# Arduino_Programmer.net
KiCad netlist of a schematic drawn in EAGLE
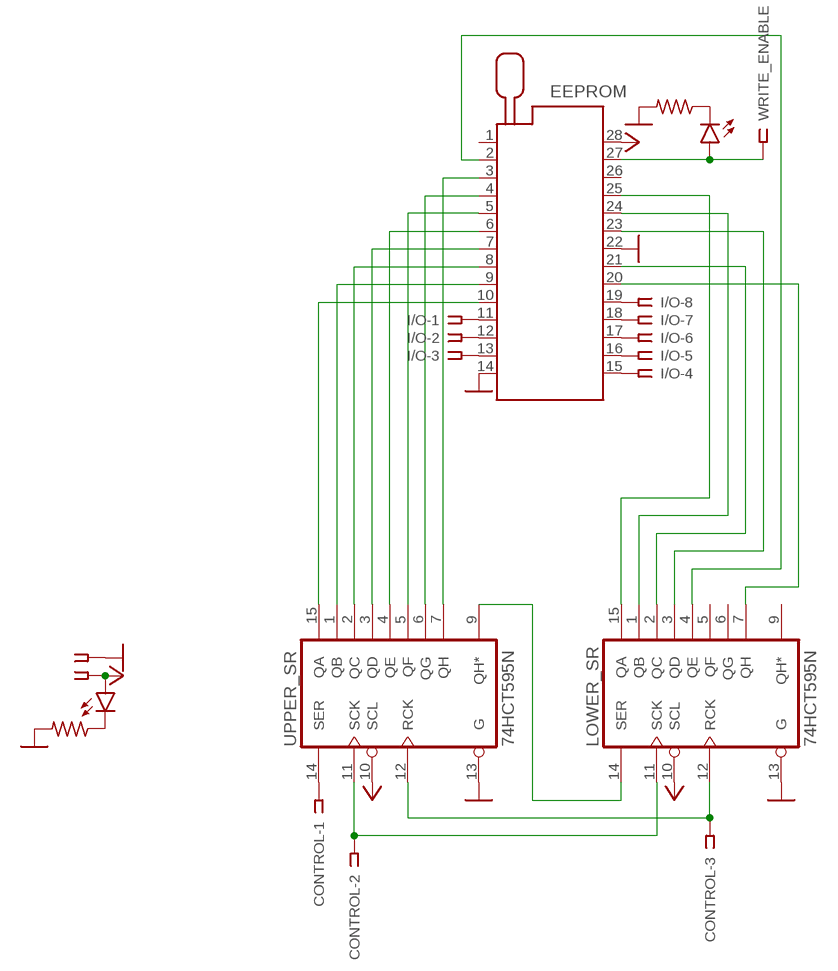
[diagram p0: schematic, sheet 1]

(export (version "E")
  (design (tool "Eeschema 10.0.6"))
  (components
    (comp (ref "CLK")
      (value "LED5MM")
      (footprint "eagle-import:LED5MM")
      (libsource (lib "eagle-import") (part "LED5MM"))
    )
    (comp (ref "CONTROL")
      (value "SSW-101-02-G-T")
      (footprint "eagle-import:SSW-101-02-G-T")
      (fields (field (name "MF") "Samtec Inc."))
      (libsource (lib "eagle-import") (part "SSW-101-02-G-T"))
    )
    (comp (ref "EEPROM")
      (value "228-1277-00-0602J")
      (footprint "eagle-import:228-1277-00-0602J")
      (fields (field (name "MF") "3M"))
      (libsource (lib "eagle-import") (part "228-?00-0602J1277-"))
    )
    (comp (ref "I/O")
      (value "SSW-108-02-G-S")
      (footprint "eagle-import:SSW-108-02-G-S")
      (fields (field (name "MF") "Samtec Inc."))
      (libsource (lib "eagle-import") (part "SSW-108-02-G-S"))
    )
    (comp (ref "LOWER_SR")
      (value "74HCT595N")
      (footprint "eagle-import:DIL16")
      (libsource (lib "eagle-import") (part "74595NHCT"))
    )
    (comp (ref "POWER")
      (value "LED5MM")
      (footprint "eagle-import:LED5MM")
      (libsource (lib "eagle-import") (part "LED5MM"))
    )
    (comp (ref "R1")
      (value "R-US_0204/7")
      (footprint "eagle-import:0204_7")
      (libsource (lib "eagle-import") (part "R-US_0204/7"))
    )
    (comp (ref "R2")
      (value "R-US_0204/7")
      (footprint "eagle-import:0204_7")
      (libsource (lib "eagle-import") (part "R-US_0204/7"))
    )
    (comp (ref "UPPER_SR")
      (value "74HCT595N")
      (footprint "eagle-import:DIL16")
      (libsource (lib "eagle-import") (part "74595NHCT"))
    )
    (comp (ref "WRITE_ENABLE")
      (value "SSW-101-02-G-S")
      (footprint "eagle-import:SSW-101-02-G-S")
      (fields (field (name "MF") "Samtec Inc."))
      (libsource (lib "eagle-import") (part "SSW-101-02-G-S"))
    )
    (comp (ref "X2")
      (value "SSW-102-02-G-S")
      (footprint "eagle-import:SSW-102-02-G-S")
      (fields (field (name "MF") "Samtec Inc."))
      (libsource (lib "eagle-import") (part "SSW-102-02-G-S"))
    )
  )
  (nets
    (net (code "1") (name "GND") (class "Default")
      (node (ref "EEPROM") (pin "14") (pinfunction "14_14") (pintype "passive"))
      (node (ref "EEPROM") (pin "22") (pinfunction "22_22") (pintype "passive"))
      (node (ref "LOWER_SR") (pin "13") (pinfunction "G_13") (pintype "input"))
      (node (ref "R1") (pin "2") (pinfunction "2_2") (pintype "passive"))
      (node (ref "R2") (pin "2") (pinfunction "2_2") (pintype "passive"))
      (node (ref "UPPER_SR") (pin "13") (pinfunction "G_13") (pintype "input"))
      (node (ref "X2") (pin "1") (pinfunction "1_1") (pintype "passive"))
    )
    (net (code "2") (name "Net-(CLK-C)") (class "Default")
      (node (ref "CLK") (pin "K") (pinfunction "C_K") (pintype "passive"))
      (node (ref "R1") (pin "1") (pinfunction "1_1") (pintype "passive"))
    )
    (net (code "3") (name "Net-(CLK-PadA)") (class "Default")
      (node (ref "CLK") (pin "A") (pinfunction "A_A") (pintype "passive"))
      (node (ref "EEPROM") (pin "27") (pinfunction "27_27") (pintype "passive"))
      (node (ref "WRITE_ENABLE") (pin "1") (pinfunction "1_1") (pintype "passive"))
    )
    (net (code "4") (name "Net-(CONTROLB-1)") (class "Default")
      (node (ref "CONTROL") (pin "2") (pinfunction "1_2") (pintype "passive"))
      (node (ref "LOWER_SR") (pin "11") (pinfunction "SCK_11") (pintype "input"))
      (node (ref "UPPER_SR") (pin "11") (pinfunction "SCK_11") (pintype "input"))
    )
    (net (code "5") (name "Net-(CONTROLC-1)") (class "Default")
      (node (ref "CONTROL") (pin "3") (pinfunction "1_3") (pintype "passive"))
      (node (ref "LOWER_SR") (pin "12") (pinfunction "RCK_12") (pintype "input"))
      (node (ref "UPPER_SR") (pin "12") (pinfunction "RCK_12") (pintype "input"))
    )
    (net (code "6") (name "Net-(EEPROM-Pad11)") (class "Default")
      (node (ref "EEPROM") (pin "11") (pinfunction "11_11") (pintype "passive"))
      (node (ref "I/O") (pin "1") (pinfunction "1_1") (pintype "passive"))
    )
    (net (code "7") (name "Net-(I/OB-1)") (class "Default")
      (node (ref "EEPROM") (pin "12") (pinfunction "12_12") (pintype "passive"))
      (node (ref "I/O") (pin "2") (pinfunction "1_2") (pintype "passive"))
    )
    (net (code "8") (name "Net-(I/OC-1)") (class "Default")
      (node (ref "EEPROM") (pin "13") (pinfunction "13_13") (pintype "passive"))
      (node (ref "I/O") (pin "3") (pinfunction "1_3") (pintype "passive"))
    )
    (net (code "9") (name "Net-(I/OD-1)") (class "Default")
      (node (ref "EEPROM") (pin "15") (pinfunction "15_15") (pintype "passive"))
      (node (ref "I/O") (pin "4") (pinfunction "1_4") (pintype "passive"))
    )
    (net (code "10") (name "Net-(I/OE-1)") (class "Default")
      (node (ref "EEPROM") (pin "16") (pinfunction "16_16") (pintype "passive"))
      (node (ref "I/O") (pin "5") (pinfunction "1_5") (pintype "passive"))
    )
    (net (code "11") (name "Net-(I/OF-1)") (class "Default")
      (node (ref "EEPROM") (pin "17") (pinfunction "17_17") (pintype "passive"))
      (node (ref "I/O") (pin "6") (pinfunction "1_6") (pintype "passive"))
    )
    (net (code "12") (name "Net-(I/OG-1)") (class "Default")
      (node (ref "EEPROM") (pin "18") (pinfunction "18_18") (pintype "passive"))
      (node (ref "I/O") (pin "7") (pinfunction "1_7") (pintype "passive"))
    )
    (net (code "13") (name "Net-(I/OH-1)") (class "Default")
      (node (ref "EEPROM") (pin "19") (pinfunction "19_19") (pintype "passive"))
      (node (ref "I/O") (pin "8") (pinfunction "1_8") (pintype "passive"))
    )
    (net (code "14") (name "Net-(LOWER_SRA-QA)") (class "Default")
      (node (ref "EEPROM") (pin "25") (pinfunction "25_25") (pintype "passive"))
      (node (ref "LOWER_SR") (pin "15") (pinfunction "QA_15") (pintype "tri_state"))
    )
    (net (code "15") (name "Net-(LOWER_SRA-QB)") (class "Default")
      (node (ref "EEPROM") (pin "24") (pinfunction "24_24") (pintype "passive"))
      (node (ref "LOWER_SR") (pin "1") (pinfunction "QB_1") (pintype "tri_state"))
    )
    (net (code "16") (name "Net-(LOWER_SRA-QC)") (class "Default")
      (node (ref "EEPROM") (pin "21") (pinfunction "21_21") (pintype "passive"))
      (node (ref "LOWER_SR") (pin "2") (pinfunction "QC_2") (pintype "tri_state"))
    )
    (net (code "17") (name "Net-(LOWER_SRA-QD)") (class "Default")
      (node (ref "EEPROM") (pin "23") (pinfunction "23_23") (pintype "passive"))
      (node (ref "LOWER_SR") (pin "3") (pinfunction "QD_3") (pintype "tri_state"))
    )
    (net (code "18") (name "Net-(LOWER_SRA-QE)") (class "Default")
      (node (ref "EEPROM") (pin "2") (pinfunction "2_2") (pintype "passive"))
      (node (ref "LOWER_SR") (pin "4") (pinfunction "QE_4") (pintype "tri_state"))
    )
    (net (code "19") (name "Net-(LOWER_SRA-QH)") (class "Default")
      (node (ref "EEPROM") (pin "20") (pinfunction "20_20") (pintype "passive"))
      (node (ref "LOWER_SR") (pin "7") (pinfunction "QH_7") (pintype "tri_state"))
    )
    (net (code "20") (name "Net-(LOWER_SRA-SER)") (class "Default")
      (node (ref "LOWER_SR") (pin "14") (pinfunction "SER_14") (pintype "input"))
      (node (ref "UPPER_SR") (pin "9") (pinfunction "QH*_9") (pintype "tri_state"))
    )
    (net (code "21") (name "Net-(POWER-C)") (class "Default")
      (node (ref "POWER") (pin "K") (pinfunction "C_K") (pintype "passive"))
      (node (ref "R2") (pin "1") (pinfunction "1_1") (pintype "passive"))
    )
    (net (code "22") (name "Net-(UPPER_SRA-QA)") (class "Default")
      (node (ref "EEPROM") (pin "10") (pinfunction "10_10") (pintype "passive"))
      (node (ref "UPPER_SR") (pin "15") (pinfunction "QA_15") (pintype "tri_state"))
    )
    (net (code "23") (name "Net-(UPPER_SRA-QB)") (class "Default")
      (node (ref "EEPROM") (pin "9") (pinfunction "9_9") (pintype "passive"))
      (node (ref "UPPER_SR") (pin "1") (pinfunction "QB_1") (pintype "tri_state"))
    )
    (net (code "24") (name "Net-(UPPER_SRA-QC)") (class "Default")
      (node (ref "EEPROM") (pin "8") (pinfunction "8_8") (pintype "passive"))
      (node (ref "UPPER_SR") (pin "2") (pinfunction "QC_2") (pintype "tri_state"))
    )
    (net (code "25") (name "Net-(UPPER_SRA-QD)") (class "Default")
      (node (ref "EEPROM") (pin "7") (pinfunction "7_7") (pintype "passive"))
      (node (ref "UPPER_SR") (pin "3") (pinfunction "QD_3") (pintype "tri_state"))
    )
    (net (code "26") (name "Net-(UPPER_SRA-QE)") (class "Default")
      (node (ref "EEPROM") (pin "6") (pinfunction "6_6") (pintype "passive"))
      (node (ref "UPPER_SR") (pin "4") (pinfunction "QE_4") (pintype "tri_state"))
    )
    (net (code "27") (name "Net-(UPPER_SRA-QF)") (class "Default")
      (node (ref "EEPROM") (pin "5") (pinfunction "5_5") (pintype "passive"))
      (node (ref "UPPER_SR") (pin "5") (pinfunction "QF_5") (pintype "tri_state"))
    )
    (net (code "28") (name "Net-(UPPER_SRA-QG)") (class "Default")
      (node (ref "EEPROM") (pin "4") (pinfunction "4_4") (pintype "passive"))
      (node (ref "UPPER_SR") (pin "6") (pinfunction "QG_6") (pintype "tri_state"))
    )
    (net (code "29") (name "Net-(UPPER_SRA-QH)") (class "Default")
      (node (ref "EEPROM") (pin "3") (pinfunction "3_3") (pintype "passive"))
      (node (ref "UPPER_SR") (pin "7") (pinfunction "QH_7") (pintype "tri_state"))
    )
    (net (code "30") (name "Net-(UPPER_SRA-SER)") (class "Default")
      (node (ref "CONTROL") (pin "1") (pinfunction "1_1") (pintype "passive"))
      (node (ref "UPPER_SR") (pin "14") (pinfunction "SER_14") (pintype "input"))
    )
    (net (code "31") (name "VCC") (class "Default")
      (node (ref "EEPROM") (pin "28") (pinfunction "28_28") (pintype "passive"))
      (node (ref "LOWER_SR") (pin "10") (pinfunction "SCL_10") (pintype "input"))
      (node (ref "POWER") (pin "A") (pinfunction "A_A") (pintype "passive"))
      (node (ref "UPPER_SR") (pin "10") (pinfunction "SCL_10") (pintype "input"))
      (node (ref "X2") (pin "2") (pinfunction "1_2") (pintype "passive"))
    )
    (net (code "32") (name "unconnected-(EEPROM-Pad1)") (class "Default")
      (node (ref "EEPROM") (pin "1") (pinfunction "1_1") (pintype "passive"))
    )
    (net (code "33") (name "unconnected-(EEPROM-Pad26)") (class "Default")
      (node (ref "EEPROM") (pin "26") (pinfunction "26_26") (pintype "passive"))
    )
    (net (code "34") (name "unconnected-(LOWER_SRA-QF-Pad5)") (class "Default")
      (node (ref "LOWER_SR") (pin "5") (pinfunction "QF_5") (pintype "tri_state"))
    )
    (net (code "35") (name "unconnected-(LOWER_SRA-QG-Pad6)") (class "Default")
      (node (ref "LOWER_SR") (pin "6") (pinfunction "QG_6") (pintype "tri_state"))
    )
    (net (code "36") (name "unconnected-(LOWER_SRA-QH*-Pad9)") (class "Default")
      (node (ref "LOWER_SR") (pin "9") (pinfunction "QH*_9") (pintype "tri_state"))
    )
  )
)
